# vca.net
KiCad netlist of a schematic drawn in EAGLE
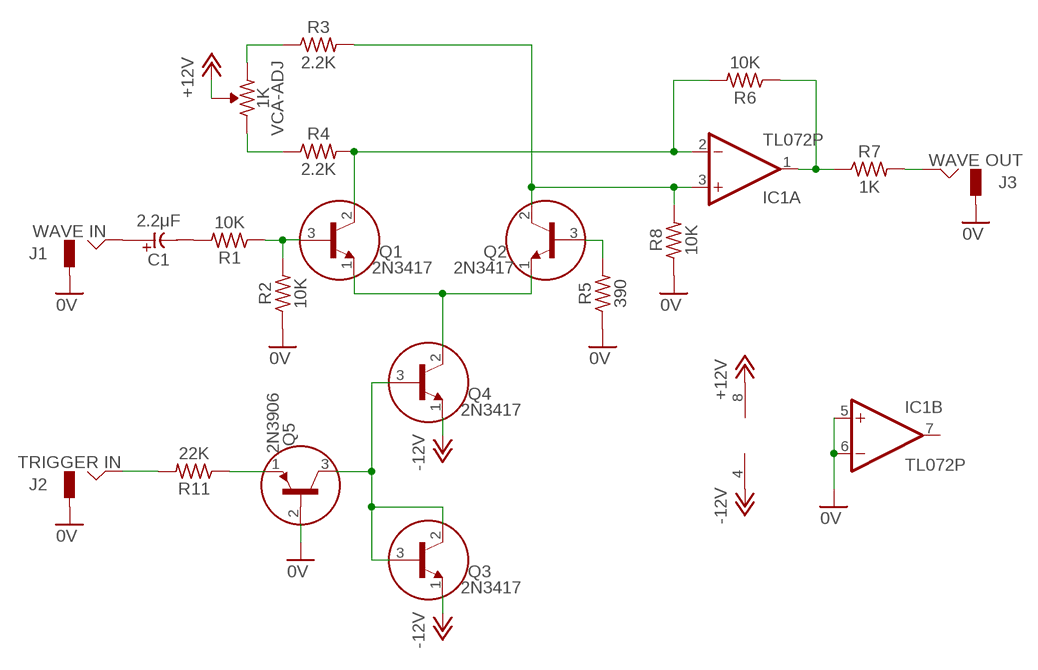
[diagram p0: schematic, sheet 1]

(export (version "E")
  (design (tool "Eeschema 10.0.6"))
  (components
    (comp (ref "C1")
      (value "2.2μF")
      (footprint "eagle-import:E2-5")
      (libsource (lib "eagle-import") (part "CE-USE2-5"))
    )
    (comp (ref "IC1")
      (value "TL072P")
      (footprint "eagle-import:DIL08")
      (libsource (lib "eagle-import") (part "TL072P"))
    )
    (comp (ref "J1")
      (value "WAVE IN")
      (footprint "eagle-import:JACK-M")
      (libsource (lib "eagle-import") (part "JACK-M"))
    )
    (comp (ref "J2")
      (value "TRIGGER IN")
      (footprint "eagle-import:JACK-M")
      (libsource (lib "eagle-import") (part "JACK-M"))
    )
    (comp (ref "J3")
      (value "WAVE OUT")
      (footprint "eagle-import:JACK-M")
      (libsource (lib "eagle-import") (part "JACK-M"))
    )
    (comp (ref "Q1")
      (value "2N3417")
      (footprint "eagle-import:TO92")
      (libsource (lib "eagle-import") (part "2N3417"))
    )
    (comp (ref "Q2")
      (value "2N3417")
      (footprint "eagle-import:TO92")
      (libsource (lib "eagle-import") (part "2N3417"))
    )
    (comp (ref "Q3")
      (value "2N3417")
      (footprint "eagle-import:TO92")
      (libsource (lib "eagle-import") (part "2N3417"))
    )
    (comp (ref "Q4")
      (value "2N3417")
      (footprint "eagle-import:TO92")
      (libsource (lib "eagle-import") (part "2N3417"))
    )
    (comp (ref "Q5")
      (value "2N3906")
      (footprint "eagle-import:TO92")
      (libsource (lib "eagle-import") (part "2N3906"))
    )
    (comp (ref "R1")
      (value "10K")
      (footprint "eagle-import:0309_10")
      (libsource (lib "eagle-import") (part "R0309/10"))
    )
    (comp (ref "R2")
      (value "10K")
      (footprint "eagle-import:0309_10")
      (libsource (lib "eagle-import") (part "R0309/10"))
    )
    (comp (ref "R3")
      (value "2.2K")
      (footprint "eagle-import:0309_10")
      (libsource (lib "eagle-import") (part "R0309/10"))
    )
    (comp (ref "R4")
      (value "2.2K")
      (footprint "eagle-import:0309_10")
      (libsource (lib "eagle-import") (part "R0309/10"))
    )
    (comp (ref "R5")
      (value "390")
      (footprint "eagle-import:0309_10")
      (libsource (lib "eagle-import") (part "R0309/10"))
    )
    (comp (ref "R6")
      (value "10K")
      (footprint "eagle-import:0309_10")
      (libsource (lib "eagle-import") (part "R0309/10"))
    )
    (comp (ref "R7")
      (value "1K")
      (footprint "eagle-import:0309_10")
      (libsource (lib "eagle-import") (part "R0309/10"))
    )
    (comp (ref "R8")
      (value "10K")
      (footprint "eagle-import:0309_10")
      (libsource (lib "eagle-import") (part "R0309/10"))
    )
    (comp (ref "R11")
      (value "22K")
      (footprint "eagle-import:0309_10")
      (libsource (lib "eagle-import") (part "R0309/10"))
    )
    (comp (ref "VCA-ADJ")
      (value "1K")
      (footprint "eagle-import:R-VAR")
      (libsource (lib "eagle-import") (part "R-VAR"))
    )
  )
  (nets
    (net (code "1") (name "+12V") (class "Default")
      (node (ref "IC1") (pin "8") (pinfunction "V+_8") (pintype "power_in"))
      (node (ref "VCA-ADJ") (pin "VAR") (pinfunction "P$1_VAR") (pintype "passive"))
    )
    (net (code "2") (name "-12V") (class "Default")
      (node (ref "IC1") (pin "4") (pinfunction "V-_4") (pintype "power_in"))
      (node (ref "Q3") (pin "1") (pinfunction "E_1") (pintype "passive"))
      (node (ref "Q4") (pin "1") (pinfunction "E_1") (pintype "passive"))
    )
    (net (code "3") (name "0V") (class "Default")
      (node (ref "IC1") (pin "5") (pinfunction "+IN_5") (pintype "input"))
      (node (ref "IC1") (pin "6") (pinfunction "-IN_6") (pintype "input"))
      (node (ref "J1") (pin "GND") (pinfunction "GND_GND") (pintype "bidirectional"))
      (node (ref "J2") (pin "GND") (pinfunction "GND_GND") (pintype "bidirectional"))
      (node (ref "J3") (pin "GND") (pinfunction "GND_GND") (pintype "bidirectional"))
      (node (ref "Q5") (pin "2") (pinfunction "B_2") (pintype "passive"))
      (node (ref "R2") (pin "1") (pinfunction "1_1") (pintype "passive"))
      (node (ref "R5") (pin "1") (pinfunction "1_1") (pintype "passive"))
      (node (ref "R8") (pin "1") (pinfunction "1_1") (pintype "passive"))
    )
    (net (code "4") (name "Net-(C1-Pad+)") (class "Default")
      (node (ref "C1") (pin "+") (pinfunction "+_+") (pintype "passive"))
      (node (ref "J1") (pin "HOT") (pinfunction "HOT_HOT") (pintype "bidirectional"))
    )
    (net (code "5") (name "Net-(C1-Pad-)") (class "Default")
      (node (ref "C1") (pin "-") (pinfunction "-_-") (pintype "passive"))
      (node (ref "R1") (pin "2") (pinfunction "2_2") (pintype "passive"))
    )
    (net (code "6") (name "Net-(IC1A-+IN)") (class "Default")
      (node (ref "IC1") (pin "3") (pinfunction "+IN_3") (pintype "input"))
      (node (ref "Q2") (pin "2") (pinfunction "C_2") (pintype "passive"))
      (node (ref "R3") (pin "2") (pinfunction "2_2") (pintype "passive"))
      (node (ref "R8") (pin "2") (pinfunction "2_2") (pintype "passive"))
    )
    (net (code "7") (name "Net-(IC1A--IN)") (class "Default")
      (node (ref "IC1") (pin "2") (pinfunction "-IN_2") (pintype "input"))
      (node (ref "Q1") (pin "2") (pinfunction "C_2") (pintype "passive"))
      (node (ref "R4") (pin "2") (pinfunction "2_2") (pintype "passive"))
      (node (ref "R6") (pin "2") (pinfunction "2_2") (pintype "passive"))
    )
    (net (code "8") (name "Net-(IC1A-OUT)") (class "Default")
      (node (ref "IC1") (pin "1") (pinfunction "OUT_1") (pintype "output"))
      (node (ref "R6") (pin "1") (pinfunction "1_1") (pintype "passive"))
      (node (ref "R7") (pin "1") (pinfunction "1_1") (pintype "passive"))
    )
    (net (code "9") (name "Net-(J2-PadHOT)") (class "Default")
      (node (ref "J2") (pin "HOT") (pinfunction "HOT_HOT") (pintype "bidirectional"))
      (node (ref "R11") (pin "2") (pinfunction "2_2") (pintype "passive"))
    )
    (net (code "10") (name "Net-(J3-PadHOT)") (class "Default")
      (node (ref "J3") (pin "HOT") (pinfunction "HOT_HOT") (pintype "bidirectional"))
      (node (ref "R7") (pin "2") (pinfunction "2_2") (pintype "passive"))
    )
    (net (code "11") (name "Net-(Q1-B)") (class "Default")
      (node (ref "Q1") (pin "3") (pinfunction "B_3") (pintype "passive"))
      (node (ref "R1") (pin "1") (pinfunction "1_1") (pintype "passive"))
      (node (ref "R2") (pin "2") (pinfunction "2_2") (pintype "passive"))
    )
    (net (code "12") (name "Net-(Q1-E)") (class "Default")
      (node (ref "Q1") (pin "1") (pinfunction "E_1") (pintype "passive"))
      (node (ref "Q2") (pin "1") (pinfunction "E_1") (pintype "passive"))
      (node (ref "Q4") (pin "2") (pinfunction "C_2") (pintype "passive"))
    )
    (net (code "13") (name "Net-(Q2-B)") (class "Default")
      (node (ref "Q2") (pin "3") (pinfunction "B_3") (pintype "passive"))
      (node (ref "R5") (pin "2") (pinfunction "2_2") (pintype "passive"))
    )
    (net (code "14") (name "Net-(Q3-B)") (class "Default")
      (node (ref "Q3") (pin "2") (pinfunction "C_2") (pintype "passive"))
      (node (ref "Q3") (pin "3") (pinfunction "B_3") (pintype "passive"))
      (node (ref "Q4") (pin "3") (pinfunction "B_3") (pintype "passive"))
      (node (ref "Q5") (pin "3") (pinfunction "C_3") (pintype "passive"))
    )
    (net (code "15") (name "Net-(Q5-E)") (class "Default")
      (node (ref "Q5") (pin "1") (pinfunction "E_1") (pintype "passive"))
      (node (ref "R11") (pin "1") (pinfunction "1_1") (pintype "passive"))
    )
    (net (code "16") (name "Net-(VCA-ADJ-1)") (class "Default")
      (node (ref "R4") (pin "1") (pinfunction "1_1") (pintype "passive"))
      (node (ref "VCA-ADJ") (pin "R1") (pinfunction "1_R1") (pintype "passive"))
    )
    (net (code "17") (name "Net-(VCA-ADJ-2)") (class "Default")
      (node (ref "R3") (pin "1") (pinfunction "1_1") (pintype "passive"))
      (node (ref "VCA-ADJ") (pin "R2") (pinfunction "2_R2") (pintype "passive"))
    )
    (net (code "18") (name "unconnected-(IC1B-OUT-Pad7)") (class "Default")
      (node (ref "IC1") (pin "7") (pinfunction "OUT_7") (pintype "output"))
    )
  )
)
